# mapleCUL_small_56.net
KiCad netlist of a schematic drawn in EAGLE
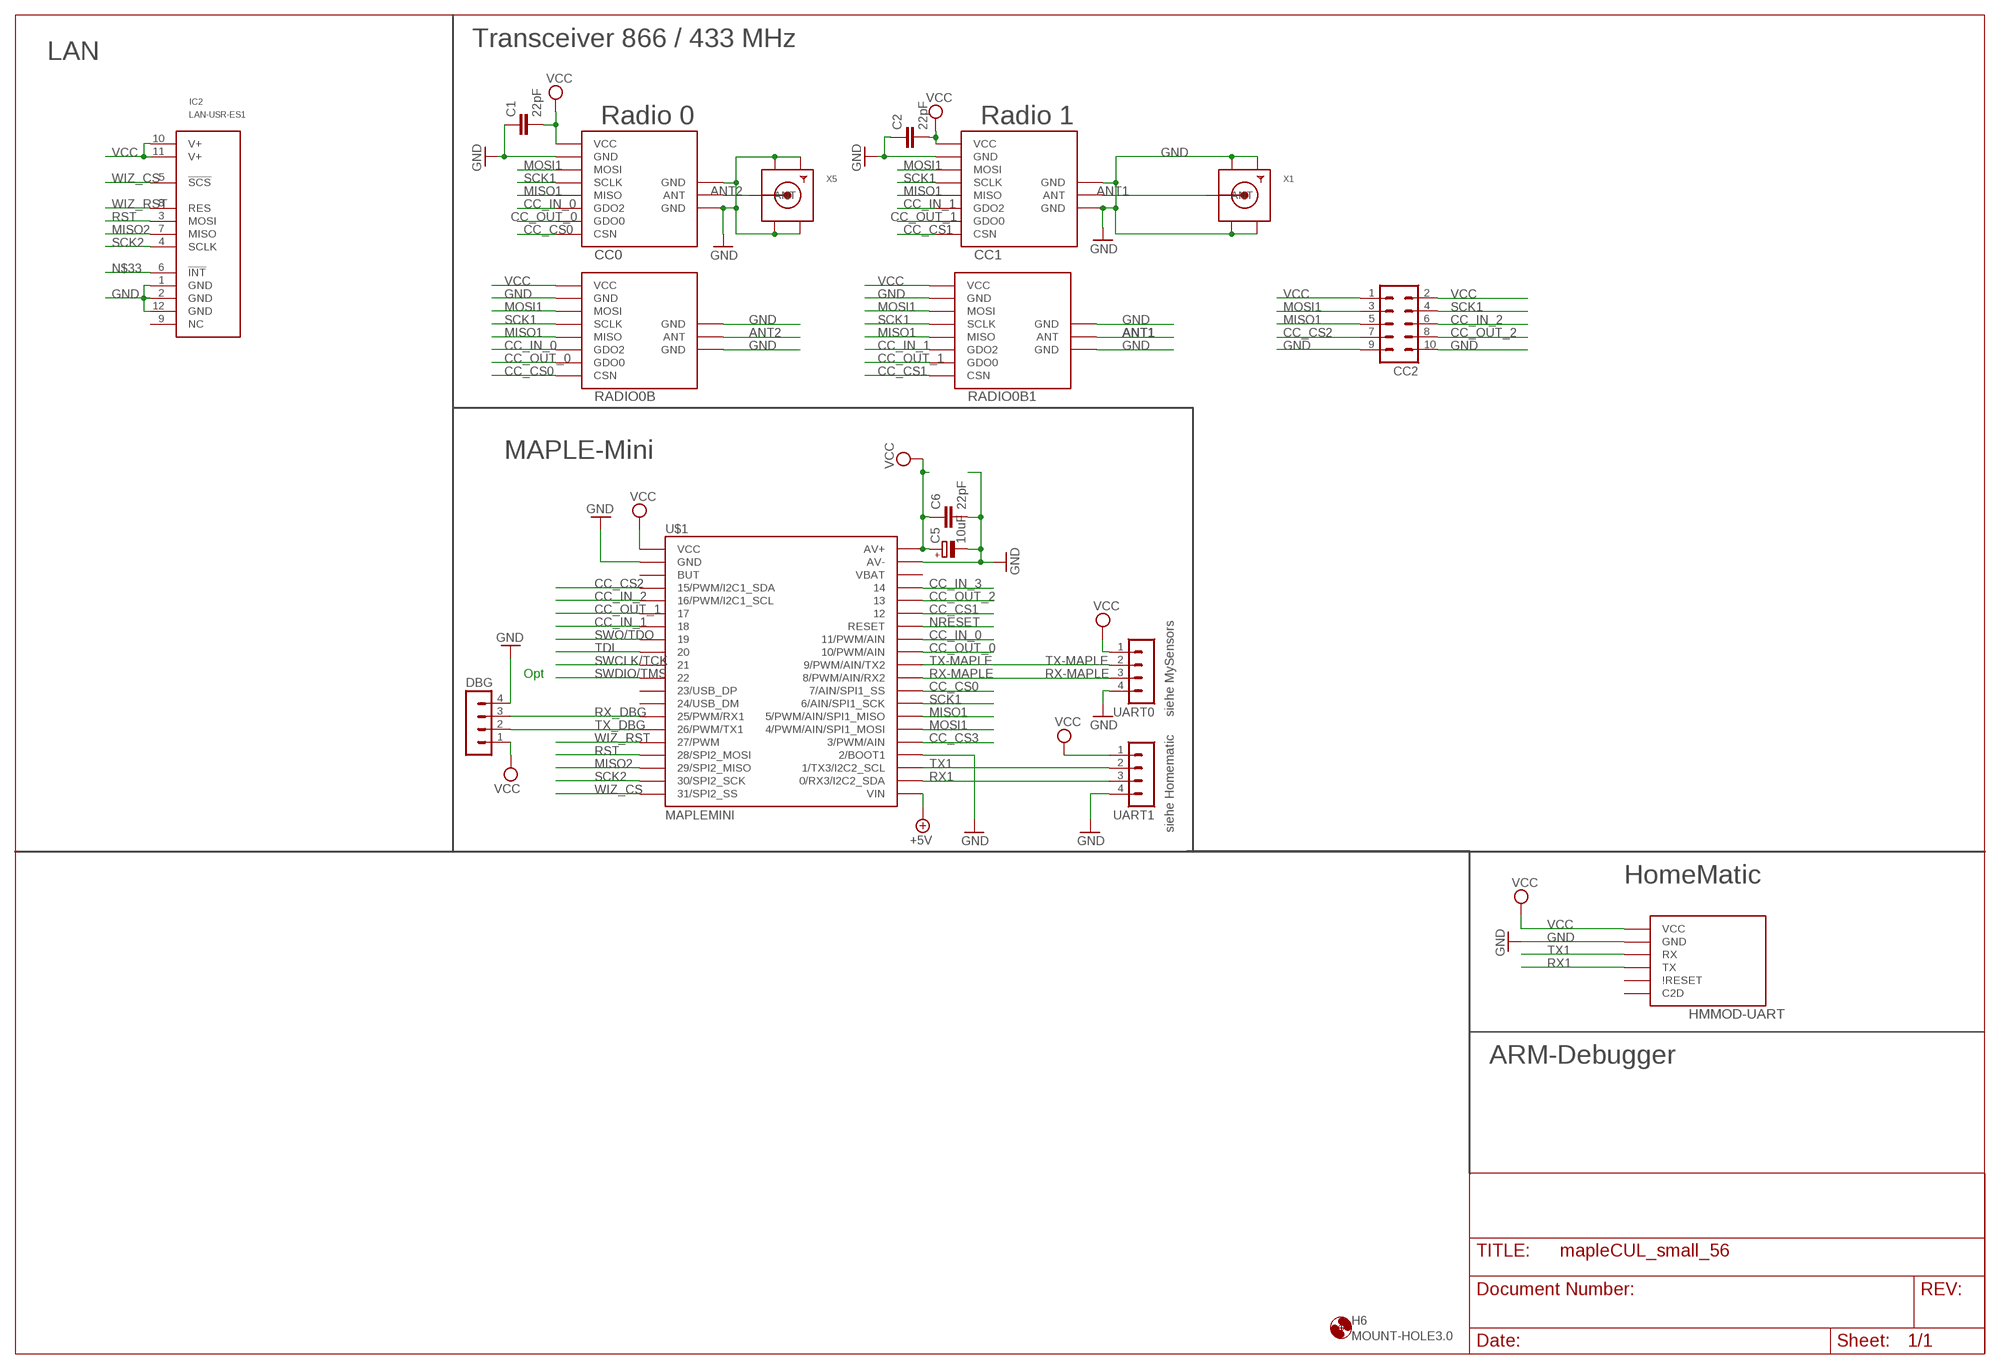
[diagram p0: schematic, sheet 1]

(export (version "E")
  (design (tool "Eeschema 10.0.6"))
  (components
    (comp (ref "C1")
      (value "22pF")
      (footprint "eagle-import:C0805")
      (libsource (lib "eagle-import") (part "C-EUC0805"))
    )
    (comp (ref "C2")
      (value "22pF")
      (footprint "eagle-import:C0805")
      (libsource (lib "eagle-import") (part "C-EUC0805"))
    )
    (comp (ref "C5")
      (value "10uF")
      (footprint "eagle-import:R_2012-12W")
      (libsource (lib "eagle-import") (part "CPOL-EUR/2012-12W"))
    )
    (comp (ref "C6")
      (value "22pF")
      (footprint "eagle-import:C0805")
      (libsource (lib "eagle-import") (part "C-EUC0805"))
    )
    (comp (ref "CC0")
      (value "CC1101")
      (footprint "eagle-import:CC1101_MODULE1_SMD")
      (libsource (lib "eagle-import") (part "wireless_CC1101_MODULE1SMD"))
    )
    (comp (ref "CC1")
      (value "CC1101_MODULE1SMD")
      (footprint "eagle-import:CC1101_MODULE1_SMD")
      (libsource (lib "eagle-import") (part "wireless_CC1101_MODULE1SMD"))
    )
    (comp (ref "CC2")
      (value "MA05-2")
      (footprint "eagle-import:MA05-2")
      (libsource (lib "eagle-import") (part "MA05-2"))
    )
    (comp (ref "DBG")
      (value "MA04-1")
      (footprint "eagle-import:MA04-1")
      (libsource (lib "eagle-import") (part "MA04-1"))
    )
    (comp (ref "H6")
      (value "MOUNT-HOLE3.0")
      (footprint "eagle-import:3,0")
      (libsource (lib "eagle-import") (part "MOUNT-HOLE3.0"))
    )
    (comp (ref "HMMOD-UART")
      (value "HM-MOD-UARTDIL")
      (footprint "eagle-import:HM-MOD-UART-DIL")
      (libsource (lib "eagle-import") (part "HM-MOD-UARTDIL"))
    )
    (comp (ref "IC2")
      (value "LAN-USR-ES1")
      (footprint "eagle-import:USR-ES1")
      (libsource (lib "eagle-import") (part "LAN-USR-ES1"))
    )
    (comp (ref "RADIO0B")
      (value "CC1101_MODULE1SMALL")
      (footprint "eagle-import:CC1101_MODULE1_SMD")
      (libsource (lib "eagle-import") (part "CC1101_MODULE1SMALL"))
    )
    (comp (ref "RADIO0B1")
      (value "CC1101_MODULE1SMALL")
      (footprint "eagle-import:CC1101_MODULE1_SMD")
      (libsource (lib "eagle-import") (part "CC1101_MODULE1SMALL"))
    )
    (comp (ref "U$1")
      (value "MAPLEMINI")
      (footprint "eagle-import:20-DIP")
      (libsource (lib "eagle-import") (part "MAPLEMINI"))
    )
    (comp (ref "UART0")
      (value "MA04-1")
      (footprint "eagle-import:MA04-1")
      (libsource (lib "eagle-import") (part "MA04-1"))
    )
    (comp (ref "UART1")
      (value "MA04-1")
      (footprint "eagle-import:MA04-1")
      (libsource (lib "eagle-import") (part "MA04-1"))
    )
    (comp (ref "X1")
      (value "SMACONNECTOR_EDGE_UFL")
      (footprint "eagle-import:SMA_EDGELAUNCH_UFL")
      (libsource (lib "eagle-import") (part "SMACONNECTOR_EDGE_UFL"))
    )
    (comp (ref "X5")
      (value "SMACONNECTOR_EDGE_UFL")
      (footprint "eagle-import:SMA_EDGELAUNCH_UFL")
      (libsource (lib "eagle-import") (part "SMACONNECTOR_EDGE_UFL"))
    )
  )
  (nets
    (net (code "1") (name "+5V") (class "Default")
      (node (ref "U$1") (pin "21") (pinfunction "VIN_21") (pintype "bidirectional"))
    )
    (net (code "2") (name "/ANT1") (class "Default")
      (node (ref "CC1") (pin "ANT") (pinfunction "ANT_ANT") (pintype "output"))
      (node (ref "RADIO0B1") (pin "ANT") (pinfunction "ANT_ANT") (pintype "output"))
      (node (ref "X1") (pin "P") (pinfunction "ANT_P") (pintype "bidirectional"))
    )
    (net (code "3") (name "/ANT2") (class "Default")
      (node (ref "CC0") (pin "ANT") (pinfunction "ANT_ANT") (pintype "output"))
      (node (ref "RADIO0B") (pin "ANT") (pinfunction "ANT_ANT") (pintype "output"))
      (node (ref "X5") (pin "P") (pinfunction "ANT_P") (pintype "bidirectional"))
    )
    (net (code "4") (name "/CC_CS0") (class "Default")
      (node (ref "CC0") (pin "CSN") (pinfunction "CSN_CSN") (pintype "bidirectional"))
      (node (ref "RADIO0B") (pin "CSN") (pinfunction "CSN_CSN") (pintype "bidirectional"))
      (node (ref "U$1") (pin "29") (pinfunction "7/AIN/SPI1_SS_29") (pintype "bidirectional"))
    )
    (net (code "5") (name "/CC_CS1") (class "Default")
      (node (ref "CC1") (pin "CSN") (pinfunction "CSN_CSN") (pintype "bidirectional"))
      (node (ref "RADIO0B1") (pin "CSN") (pinfunction "CSN_CSN") (pintype "bidirectional"))
      (node (ref "U$1") (pin "35") (pinfunction "12_35") (pintype "bidirectional"))
    )
    (net (code "6") (name "/CC_CS2") (class "Default")
      (node (ref "CC2") (pin "7") (pinfunction "7_7") (pintype "passive"))
      (node (ref "U$1") (pin "4") (pinfunction "15/PWM/I2C1_SDA_4") (pintype "bidirectional"))
    )
    (net (code "7") (name "/CC_CS3") (class "Default")
      (node (ref "U$1") (pin "25") (pinfunction "3/PWM/AIN_25") (pintype "bidirectional"))
    )
    (net (code "8") (name "/CC_IN_0") (class "Default")
      (node (ref "CC0") (pin "GDO2") (pinfunction "GDO2_GDO2") (pintype "bidirectional"))
      (node (ref "RADIO0B") (pin "GDO2") (pinfunction "GDO2_GDO2") (pintype "bidirectional"))
      (node (ref "U$1") (pin "33") (pinfunction "11/PWM/AIN_33") (pintype "bidirectional"))
    )
    (net (code "9") (name "/CC_IN_1") (class "Default")
      (node (ref "CC1") (pin "GDO2") (pinfunction "GDO2_GDO2") (pintype "bidirectional"))
      (node (ref "RADIO0B1") (pin "GDO2") (pinfunction "GDO2_GDO2") (pintype "bidirectional"))
      (node (ref "U$1") (pin "7") (pinfunction "18_7") (pintype "bidirectional"))
    )
    (net (code "10") (name "/CC_IN_2") (class "Default")
      (node (ref "CC2") (pin "6") (pinfunction "6_6") (pintype "passive"))
      (node (ref "U$1") (pin "5") (pinfunction "16/PWM/I2C1_SCL_5") (pintype "bidirectional"))
    )
    (net (code "11") (name "/CC_IN_3") (class "Default")
      (node (ref "U$1") (pin "37") (pinfunction "14_37") (pintype "bidirectional"))
    )
    (net (code "12") (name "/CC_OUT_0") (class "Default")
      (node (ref "CC0") (pin "GDO0") (pinfunction "GDO0_GDO0") (pintype "bidirectional"))
      (node (ref "RADIO0B") (pin "GDO0") (pinfunction "GDO0_GDO0") (pintype "bidirectional"))
      (node (ref "U$1") (pin "32") (pinfunction "10/PWM/AIN_32") (pintype "bidirectional"))
    )
    (net (code "13") (name "/CC_OUT_1") (class "Default")
      (node (ref "CC1") (pin "GDO0") (pinfunction "GDO0_GDO0") (pintype "bidirectional"))
      (node (ref "RADIO0B1") (pin "GDO0") (pinfunction "GDO0_GDO0") (pintype "bidirectional"))
      (node (ref "U$1") (pin "6") (pinfunction "17_6") (pintype "bidirectional"))
    )
    (net (code "14") (name "/CC_OUT_2") (class "Default")
      (node (ref "CC2") (pin "8") (pinfunction "8_8") (pintype "passive"))
      (node (ref "U$1") (pin "36") (pinfunction "13_36") (pintype "bidirectional"))
    )
    (net (code "15") (name "/MISO1") (class "Default")
      (node (ref "CC0") (pin "MISO") (pinfunction "MISO_MISO") (pintype "bidirectional"))
      (node (ref "CC1") (pin "MISO") (pinfunction "MISO_MISO") (pintype "bidirectional"))
      (node (ref "CC2") (pin "5") (pinfunction "5_5") (pintype "passive"))
      (node (ref "RADIO0B") (pin "MISO") (pinfunction "MISO_MISO") (pintype "bidirectional"))
      (node (ref "RADIO0B1") (pin "MISO") (pinfunction "MISO_MISO") (pintype "bidirectional"))
      (node (ref "U$1") (pin "27") (pinfunction "5/PWM/AIN/SPI1_MISO_27") (pintype "bidirectional"))
    )
    (net (code "16") (name "/MISO2") (class "Default")
      (node (ref "IC2") (pin "7") (pinfunction "MISO_7") (pintype "bidirectional"))
      (node (ref "U$1") (pin "18") (pinfunction "29/SPI2_MISO_18") (pintype "bidirectional"))
    )
    (net (code "17") (name "/MOSI1") (class "Default")
      (node (ref "CC0") (pin "MOSI") (pinfunction "MOSI_MOSI") (pintype "bidirectional"))
      (node (ref "CC1") (pin "MOSI") (pinfunction "MOSI_MOSI") (pintype "bidirectional"))
      (node (ref "CC2") (pin "3") (pinfunction "3_3") (pintype "passive"))
      (node (ref "RADIO0B") (pin "MOSI") (pinfunction "MOSI_MOSI") (pintype "bidirectional"))
      (node (ref "RADIO0B1") (pin "MOSI") (pinfunction "MOSI_MOSI") (pintype "bidirectional"))
      (node (ref "U$1") (pin "26") (pinfunction "4/PWM/AIN/SPI1_MOSI_26") (pintype "bidirectional"))
    )
    (net (code "18") (name "/N$33") (class "Default")
      (node (ref "IC2") (pin "6") (pinfunction "~{INT}_6") (pintype "output"))
    )
    (net (code "19") (name "/NRESET") (class "Default")
      (node (ref "U$1") (pin "34") (pinfunction "RESET_34") (pintype "bidirectional"))
    )
    (net (code "20") (name "/RST") (class "Default")
      (node (ref "IC2") (pin "3") (pinfunction "MOSI_3") (pintype "bidirectional"))
      (node (ref "U$1") (pin "17") (pinfunction "28/SPI2_MOSI_17") (pintype "bidirectional"))
    )
    (net (code "21") (name "/RX-MAPLE") (class "Default")
      (node (ref "U$1") (pin "30") (pinfunction "8/PWM/AIN/RX2_30") (pintype "bidirectional"))
      (node (ref "UART0") (pin "3") (pinfunction "3_3") (pintype "passive"))
    )
    (net (code "22") (name "/RX1") (class "Default")
      (node (ref "HMMOD-UART") (pin "5") (pinfunction "TX_5") (pintype "bidirectional"))
      (node (ref "U$1") (pin "22") (pinfunction "0/RX3/I2C2_SDA_22") (pintype "bidirectional"))
      (node (ref "UART1") (pin "3") (pinfunction "3_3") (pintype "passive"))
    )
    (net (code "23") (name "/RX_DBG") (class "Default")
      (node (ref "DBG") (pin "3") (pinfunction "3_3") (pintype "passive"))
      (node (ref "U$1") (pin "14") (pinfunction "25/PWM/RX1_14") (pintype "bidirectional"))
    )
    (net (code "24") (name "/SCK1") (class "Default")
      (node (ref "CC0") (pin "SCLK") (pinfunction "SCLK_SCLK") (pintype "bidirectional"))
      (node (ref "CC1") (pin "SCLK") (pinfunction "SCLK_SCLK") (pintype "bidirectional"))
      (node (ref "CC2") (pin "4") (pinfunction "4_4") (pintype "passive"))
      (node (ref "RADIO0B") (pin "SCLK") (pinfunction "SCLK_SCLK") (pintype "bidirectional"))
      (node (ref "RADIO0B1") (pin "SCLK") (pinfunction "SCLK_SCLK") (pintype "bidirectional"))
      (node (ref "U$1") (pin "28") (pinfunction "6/AIN/SPI1_SCK_28") (pintype "bidirectional"))
    )
    (net (code "25") (name "/SCK2") (class "Default")
      (node (ref "IC2") (pin "4") (pinfunction "SCLK_4") (pintype "input"))
      (node (ref "U$1") (pin "19") (pinfunction "30/SPI2_SCK_19") (pintype "bidirectional"))
    )
    (net (code "26") (name "/SWCLK{slash}TCK") (class "Default")
      (node (ref "U$1") (pin "10") (pinfunction "21_10") (pintype "bidirectional"))
    )
    (net (code "27") (name "/SWDIO{slash}TMS") (class "Default")
      (node (ref "U$1") (pin "11") (pinfunction "22_11") (pintype "bidirectional"))
    )
    (net (code "28") (name "/SWO{slash}TDO") (class "Default")
      (node (ref "U$1") (pin "8") (pinfunction "19_8") (pintype "bidirectional"))
    )
    (net (code "29") (name "/TDI") (class "Default")
      (node (ref "U$1") (pin "9") (pinfunction "20_9") (pintype "bidirectional"))
    )
    (net (code "30") (name "/TX-MAPLE") (class "Default")
      (node (ref "U$1") (pin "31") (pinfunction "9/PWM/AIN/TX2_31") (pintype "bidirectional"))
      (node (ref "UART0") (pin "2") (pinfunction "2_2") (pintype "passive"))
    )
    (net (code "31") (name "/TX1") (class "Default")
      (node (ref "HMMOD-UART") (pin "6") (pinfunction "RX_6") (pintype "bidirectional"))
      (node (ref "U$1") (pin "23") (pinfunction "1/TX3/I2C2_SCL_23") (pintype "bidirectional"))
      (node (ref "UART1") (pin "2") (pinfunction "2_2") (pintype "passive"))
    )
    (net (code "32") (name "/TX_DBG") (class "Default")
      (node (ref "DBG") (pin "2") (pinfunction "2_2") (pintype "passive"))
      (node (ref "U$1") (pin "15") (pinfunction "26/PWM/TX1_15") (pintype "bidirectional"))
    )
    (net (code "33") (name "/WIZ_CS") (class "Default")
      (node (ref "IC2") (pin "5") (pinfunction "~{SCS}_5") (pintype "input"))
      (node (ref "U$1") (pin "20") (pinfunction "31/SPI2_SS_20") (pintype "bidirectional"))
    )
    (net (code "34") (name "/WIZ_RST") (class "Default")
      (node (ref "IC2") (pin "8") (pinfunction "RES_8") (pintype "input"))
      (node (ref "U$1") (pin "16") (pinfunction "27/PWM_16") (pintype "bidirectional"))
    )
    (net (code "35") (name "GND") (class "Default")
      (node (ref "C1") (pin "1") (pinfunction "1_1") (pintype "passive"))
      (node (ref "C2") (pin "1") (pinfunction "1_1") (pintype "passive"))
      (node (ref "C5") (pin "-") (pinfunction "-_-") (pintype "passive"))
      (node (ref "C6") (pin "2") (pinfunction "2_2") (pintype "passive"))
      (node (ref "CC0") (pin "GND@0") (pinfunction "GND_GND@0") (pintype "power_in"))
      (node (ref "CC0") (pin "GND@1") (pinfunction "GND_GND@1") (pintype "power_in"))
      (node (ref "CC0") (pin "GND@2") (pinfunction "GND_GND@2") (pintype "power_in"))
      (node (ref "CC1") (pin "GND@0") (pinfunction "GND_GND@0") (pintype "power_in"))
      (node (ref "CC1") (pin "GND@1") (pinfunction "GND_GND@1") (pintype "power_in"))
      (node (ref "CC1") (pin "GND@2") (pinfunction "GND_GND@2") (pintype "power_in"))
      (node (ref "CC2") (pin "10") (pinfunction "10_10") (pintype "passive"))
      (node (ref "CC2") (pin "9") (pinfunction "9_9") (pintype "passive"))
      (node (ref "DBG") (pin "4") (pinfunction "4_4") (pintype "passive"))
      (node (ref "HMMOD-UART") (pin "2") (pinfunction "GND_2") (pintype "power_in"))
      (node (ref "IC2") (pin "1") (pinfunction "GND_1") (pintype "power_in"))
      (node (ref "IC2") (pin "12") (pinfunction "GND_12") (pintype "power_in"))
      (node (ref "IC2") (pin "2") (pinfunction "GND_2") (pintype "power_in"))
      (node (ref "RADIO0B") (pin "GND@0") (pinfunction "GND_GND@0") (pintype "power_in"))
      (node (ref "RADIO0B") (pin "GND@1") (pinfunction "GND_GND@1") (pintype "power_in"))
      (node (ref "RADIO0B") (pin "GND@2") (pinfunction "GND_GND@2") (pintype "power_in"))
      (node (ref "RADIO0B1") (pin "GND@0") (pinfunction "GND_GND@0") (pintype "power_in"))
      (node (ref "RADIO0B1") (pin "GND@1") (pinfunction "GND_GND@1") (pintype "power_in"))
      (node (ref "RADIO0B1") (pin "GND@2") (pinfunction "GND_GND@2") (pintype "power_in"))
      (node (ref "U$1") (pin "2") (pinfunction "GND_2") (pintype "bidirectional"))
      (node (ref "U$1") (pin "24") (pinfunction "2/BOOT1_24") (pintype "bidirectional"))
      (node (ref "U$1") (pin "39") (pinfunction "AV-_39") (pintype "bidirectional"))
      (node (ref "UART0") (pin "4") (pinfunction "4_4") (pintype "passive"))
      (node (ref "UART1") (pin "4") (pinfunction "4_4") (pintype "passive"))
      (node (ref "X1") (pin "GND@1") (pinfunction "GND1_GND@1") (pintype "power_in"))
      (node (ref "X1") (pin "GND@2") (pinfunction "GND2_GND@2") (pintype "power_in"))
      (node (ref "X1") (pin "GND@3") (pinfunction "GND3_GND@3") (pintype "power_in"))
      (node (ref "X1") (pin "GND@4") (pinfunction "GND4_GND@4") (pintype "power_in"))
      (node (ref "X5") (pin "GND@1") (pinfunction "GND1_GND@1") (pintype "power_in"))
      (node (ref "X5") (pin "GND@2") (pinfunction "GND2_GND@2") (pintype "power_in"))
      (node (ref "X5") (pin "GND@3") (pinfunction "GND3_GND@3") (pintype "power_in"))
      (node (ref "X5") (pin "GND@4") (pinfunction "GND4_GND@4") (pintype "power_in"))
    )
    (net (code "36") (name "VCC") (class "Default")
      (node (ref "C1") (pin "2") (pinfunction "2_2") (pintype "passive"))
      (node (ref "C2") (pin "2") (pinfunction "2_2") (pintype "passive"))
      (node (ref "C5") (pin "+") (pinfunction "+_+") (pintype "passive"))
      (node (ref "C6") (pin "1") (pinfunction "1_1") (pintype "passive"))
      (node (ref "CC0") (pin "VCC") (pinfunction "VCC_VCC") (pintype "power_in"))
      (node (ref "CC1") (pin "VCC") (pinfunction "VCC_VCC") (pintype "power_in"))
      (node (ref "CC2") (pin "1") (pinfunction "1_1") (pintype "passive"))
      (node (ref "CC2") (pin "2") (pinfunction "2_2") (pintype "passive"))
      (node (ref "DBG") (pin "1") (pinfunction "1_1") (pintype "passive"))
      (node (ref "HMMOD-UART") (pin "1") (pinfunction "VCC_1") (pintype "power_in"))
      (node (ref "IC2") (pin "10") (pinfunction "V+_10") (pintype "power_in"))
      (node (ref "IC2") (pin "11") (pinfunction "V+_11") (pintype "power_in"))
      (node (ref "RADIO0B") (pin "VCC") (pinfunction "VCC_VCC") (pintype "power_in"))
      (node (ref "RADIO0B1") (pin "VCC") (pinfunction "VCC_VCC") (pintype "power_in"))
      (node (ref "U$1") (pin "1") (pinfunction "VCC_1") (pintype "bidirectional"))
      (node (ref "U$1") (pin "40") (pinfunction "AV+_40") (pintype "bidirectional"))
      (node (ref "UART0") (pin "1") (pinfunction "1_1") (pintype "passive"))
      (node (ref "UART1") (pin "1") (pinfunction "1_1") (pintype "passive"))
    )
    (net (code "37") (name "unconnected-(HMMOD-UART-C2D-Pad3)") (class "Default")
      (node (ref "HMMOD-UART") (pin "3") (pinfunction "C2D_3") (pintype "bidirectional"))
    )
    (net (code "38") (name "unconnected-(HMMOD-UART-\\~{RESET}-Pad4)") (class "Default")
      (node (ref "HMMOD-UART") (pin "4") (pinfunction "\\~{RESET}_4") (pintype "bidirectional"))
    )
    (net (code "39") (name "unconnected-(IC2-NC-Pad9)") (class "Default")
      (node (ref "IC2") (pin "9") (pinfunction "NC_9") (pintype "no_connect"))
    )
    (net (code "40") (name "unconnected-(U$1-23{slash}USB_DP-Pad12)") (class "Default")
      (node (ref "U$1") (pin "12") (pinfunction "23/USB_DP_12") (pintype "bidirectional"))
    )
    (net (code "41") (name "unconnected-(U$1-24{slash}USB_DM-Pad13)") (class "Default")
      (node (ref "U$1") (pin "13") (pinfunction "24/USB_DM_13") (pintype "bidirectional"))
    )
    (net (code "42") (name "unconnected-(U$1-BUT-Pad3)") (class "Default")
      (node (ref "U$1") (pin "3") (pinfunction "BUT_3") (pintype "bidirectional"))
    )
    (net (code "43") (name "unconnected-(U$1-VBAT-Pad38)") (class "Default")
      (node (ref "U$1") (pin "38") (pinfunction "VBAT_38") (pintype "bidirectional"))
    )
  )
)
